# heath_monitor.net
KiCad netlist of a schematic drawn in Altium Designer
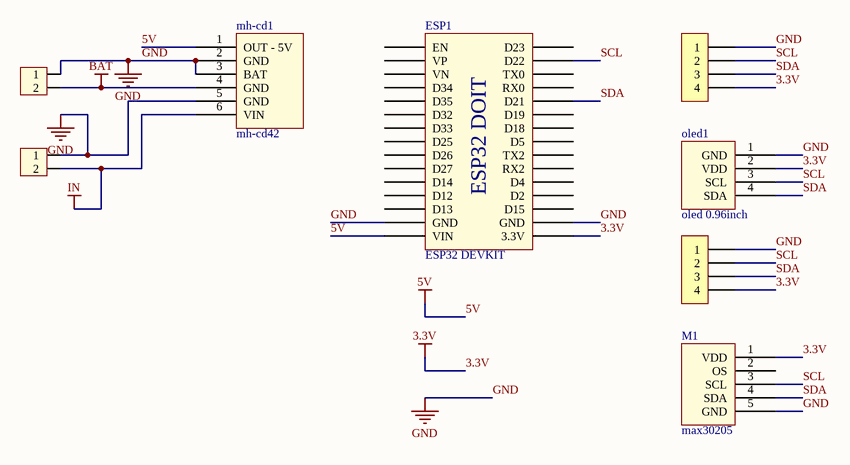
[diagram p0: heath_monitor.SchDoc]

(export (version "E")
  (design (tool "Eeschema 10.0.6"))
  (components
    (comp (ref "ESP1")
      (value "ESP32 DEVKIT")
      (footprint "ESP32 WROOM 32 KIT")
      (libsource (lib "Altium_Lib_by_KhueNguyenCreator") (part "ESP32 WROOM 32 KIT"))
    )
    (comp (ref "H1")
      (value "~")
      (footprint "Header 4P DC 2.54")
      (description "Cắm")
      (libsource (lib "Altium_Lib_by_KhueNguyenCreator") (part "Header 4P 2.54 Duc Cong"))
    )
    (comp (ref "h2")
      (value "~")
      (footprint "Header 4P DC 2.54")
      (description "Cắm")
      (libsource (lib "Altium_Lib_by_KhueNguyenCreator") (part "Header 4P 2.54 Duc Cong"))
    )
    (comp (ref "M1")
      (value "max30205")
      (footprint "max30205")
      (libsource (lib "heath_monitor_lib_by_phong") (part "max30205"))
    )
    (comp (ref "mh-cd1")
      (value "mh-cd42")
      (footprint "mh-cd42")
      (libsource (lib "heath_monitor_lib_by_phong") (part "mh-cd42"))
    )
    (comp (ref "Nguon sac")
      (value "~")
      (footprint "XH2.54M-2")
      (description "Cắm")
      (libsource (lib "Altium_Lib_by_KhueNguyenCreator") (part "Header 2P 2.54 Duc Thang"))
    )
    (comp (ref "oled1")
      (value "oled 0.96inch")
      (footprint "oled 0x96inch")
      (libsource (lib "heath_monitor_lib_by_phong") (part "oled 0.96inch"))
    )
    (comp (ref "PIN")
      (value "~")
      (footprint "XH2.54M-2")
      (description "Cắm")
      (libsource (lib "Altium_Lib_by_KhueNguyenCreator") (part "Header 2P 2.54 Duc Thang"))
    )
  )
  (nets
    (net (code "1") (name "/SCL") (class "Default")
      (node (ref "ESP1") (pin "29") (pinfunction "D22_29") (pintype "passive"))
      (node (ref "H1") (pin "2") (pinfunction "2_2") (pintype "passive"))
      (node (ref "M1") (pin "3") (pinfunction "SCL_3") (pintype "passive"))
      (node (ref "h2") (pin "2") (pinfunction "2_2") (pintype "passive"))
      (node (ref "oled1") (pin "3") (pinfunction "SCL_3") (pintype "passive"))
    )
    (net (code "2") (name "/SDA") (class "Default")
      (node (ref "ESP1") (pin "26") (pinfunction "D21_26") (pintype "passive"))
      (node (ref "H1") (pin "3") (pinfunction "3_3") (pintype "passive"))
      (node (ref "M1") (pin "4") (pinfunction "SDA_4") (pintype "passive"))
      (node (ref "h2") (pin "3") (pinfunction "3_3") (pintype "passive"))
      (node (ref "oled1") (pin "4") (pinfunction "SDA_4") (pintype "passive"))
    )
    (net (code "3") (name "3.3V") (class "Default")
      (node (ref "ESP1") (pin "16") (pinfunction "3.3V_16") (pintype "passive"))
      (node (ref "H1") (pin "4") (pinfunction "4_4") (pintype "passive"))
      (node (ref "M1") (pin "1") (pinfunction "VDD_1") (pintype "passive"))
      (node (ref "h2") (pin "4") (pinfunction "4_4") (pintype "passive"))
      (node (ref "oled1") (pin "2") (pinfunction "VDD_2") (pintype "passive"))
    )
    (net (code "4") (name "5V") (class "Default")
      (node (ref "ESP1") (pin "15") (pinfunction "VIN_15") (pintype "passive"))
      (node (ref "mh-cd1") (pin "1") (pinfunction "OUT_-_5V_1") (pintype "passive"))
    )
    (net (code "5") (name "BAT") (class "Default")
      (node (ref "PIN") (pin "2") (pinfunction "2_2") (pintype "passive"))
      (node (ref "mh-cd1") (pin "4") (pinfunction "GND_4") (pintype "passive"))
    )
    (net (code "6") (name "GND") (class "Default")
      (node (ref "ESP1") (pin "14") (pinfunction "GND_14") (pintype "passive"))
      (node (ref "ESP1") (pin "17") (pinfunction "GND_17") (pintype "passive"))
      (node (ref "H1") (pin "1") (pinfunction "1_1") (pintype "passive"))
      (node (ref "M1") (pin "5") (pinfunction "GND_5") (pintype "passive"))
      (node (ref "Nguon sac") (pin "1") (pinfunction "1_1") (pintype "passive"))
      (node (ref "PIN") (pin "1") (pinfunction "1_1") (pintype "passive"))
      (node (ref "h2") (pin "1") (pinfunction "1_1") (pintype "passive"))
      (node (ref "mh-cd1") (pin "2") (pinfunction "GND_2") (pintype "passive"))
      (node (ref "mh-cd1") (pin "3") (pinfunction "BAT_3") (pintype "passive"))
      (node (ref "mh-cd1") (pin "5") (pinfunction "GND_5") (pintype "passive"))
      (node (ref "oled1") (pin "1") (pinfunction "GND_1") (pintype "passive"))
    )
    (net (code "7") (name "IN") (class "Default")
      (node (ref "Nguon sac") (pin "2") (pinfunction "2_2") (pintype "passive"))
      (node (ref "mh-cd1") (pin "6") (pinfunction "VIN_6") (pintype "passive"))
    )
    (net (code "8") (name "unconnected-(ESP1-D2-Pad19)") (class "Default")
      (node (ref "ESP1") (pin "19") (pinfunction "D2_19") (pintype "passive"))
    )
    (net (code "9") (name "unconnected-(ESP1-D4-Pad20)") (class "Default")
      (node (ref "ESP1") (pin "20") (pinfunction "D4_20") (pintype "passive"))
    )
    (net (code "10") (name "unconnected-(ESP1-D5-Pad23)") (class "Default")
      (node (ref "ESP1") (pin "23") (pinfunction "D5_23") (pintype "passive"))
    )
    (net (code "11") (name "unconnected-(ESP1-D12-Pad12)") (class "Default")
      (node (ref "ESP1") (pin "12") (pinfunction "D12_12") (pintype "passive"))
    )
    (net (code "12") (name "unconnected-(ESP1-D13-Pad13)") (class "Default")
      (node (ref "ESP1") (pin "13") (pinfunction "D13_13") (pintype "passive"))
    )
    (net (code "13") (name "unconnected-(ESP1-D14-Pad11)") (class "Default")
      (node (ref "ESP1") (pin "11") (pinfunction "D14_11") (pintype "passive"))
    )
    (net (code "14") (name "unconnected-(ESP1-D15-Pad18)") (class "Default")
      (node (ref "ESP1") (pin "18") (pinfunction "D15_18") (pintype "passive"))
    )
    (net (code "15") (name "unconnected-(ESP1-D18-Pad24)") (class "Default")
      (node (ref "ESP1") (pin "24") (pinfunction "D18_24") (pintype "passive"))
    )
    (net (code "16") (name "unconnected-(ESP1-D19-Pad25)") (class "Default")
      (node (ref "ESP1") (pin "25") (pinfunction "D19_25") (pintype "passive"))
    )
    (net (code "17") (name "unconnected-(ESP1-D23-Pad30)") (class "Default")
      (node (ref "ESP1") (pin "30") (pinfunction "D23_30") (pintype "passive"))
    )
    (net (code "18") (name "unconnected-(ESP1-D25-Pad8)") (class "Default")
      (node (ref "ESP1") (pin "8") (pinfunction "D25_8") (pintype "passive"))
    )
    (net (code "19") (name "unconnected-(ESP1-D26-Pad9)") (class "Default")
      (node (ref "ESP1") (pin "9") (pinfunction "D26_9") (pintype "passive"))
    )
    (net (code "20") (name "unconnected-(ESP1-D27-Pad10)") (class "Default")
      (node (ref "ESP1") (pin "10") (pinfunction "D27_10") (pintype "passive"))
    )
    (net (code "21") (name "unconnected-(ESP1-D32-Pad6)") (class "Default")
      (node (ref "ESP1") (pin "6") (pinfunction "D32_6") (pintype "passive"))
    )
    (net (code "22") (name "unconnected-(ESP1-D33-Pad7)") (class "Default")
      (node (ref "ESP1") (pin "7") (pinfunction "D33_7") (pintype "passive"))
    )
    (net (code "23") (name "unconnected-(ESP1-D34-Pad4)") (class "Default")
      (node (ref "ESP1") (pin "4") (pinfunction "D34_4") (pintype "passive"))
    )
    (net (code "24") (name "unconnected-(ESP1-D35-Pad5)") (class "Default")
      (node (ref "ESP1") (pin "5") (pinfunction "D35_5") (pintype "passive"))
    )
    (net (code "25") (name "unconnected-(ESP1-EN-Pad1)") (class "Default")
      (node (ref "ESP1") (pin "1") (pinfunction "EN_1") (pintype "passive"))
    )
    (net (code "26") (name "unconnected-(ESP1-RX0-Pad27)") (class "Default")
      (node (ref "ESP1") (pin "27") (pinfunction "RX0_27") (pintype "passive"))
    )
    (net (code "27") (name "unconnected-(ESP1-RX2-Pad21)") (class "Default")
      (node (ref "ESP1") (pin "21") (pinfunction "RX2_21") (pintype "passive"))
    )
    (net (code "28") (name "unconnected-(ESP1-TX0-Pad28)") (class "Default")
      (node (ref "ESP1") (pin "28") (pinfunction "TX0_28") (pintype "passive"))
    )
    (net (code "29") (name "unconnected-(ESP1-TX2-Pad22)") (class "Default")
      (node (ref "ESP1") (pin "22") (pinfunction "TX2_22") (pintype "passive"))
    )
    (net (code "30") (name "unconnected-(ESP1-VN-Pad3)") (class "Default")
      (node (ref "ESP1") (pin "3") (pinfunction "VN_3") (pintype "passive"))
    )
    (net (code "31") (name "unconnected-(ESP1-VP-Pad2)") (class "Default")
      (node (ref "ESP1") (pin "2") (pinfunction "VP_2") (pintype "passive"))
    )
    (net (code "32") (name "unconnected-(M1-OS-Pad2)") (class "Default")
      (node (ref "M1") (pin "2") (pinfunction "OS_2") (pintype "passive"))
    )
  )
)
